# bpod_stepper_1_4_3.net
KiCad netlist of a schematic drawn in EAGLE
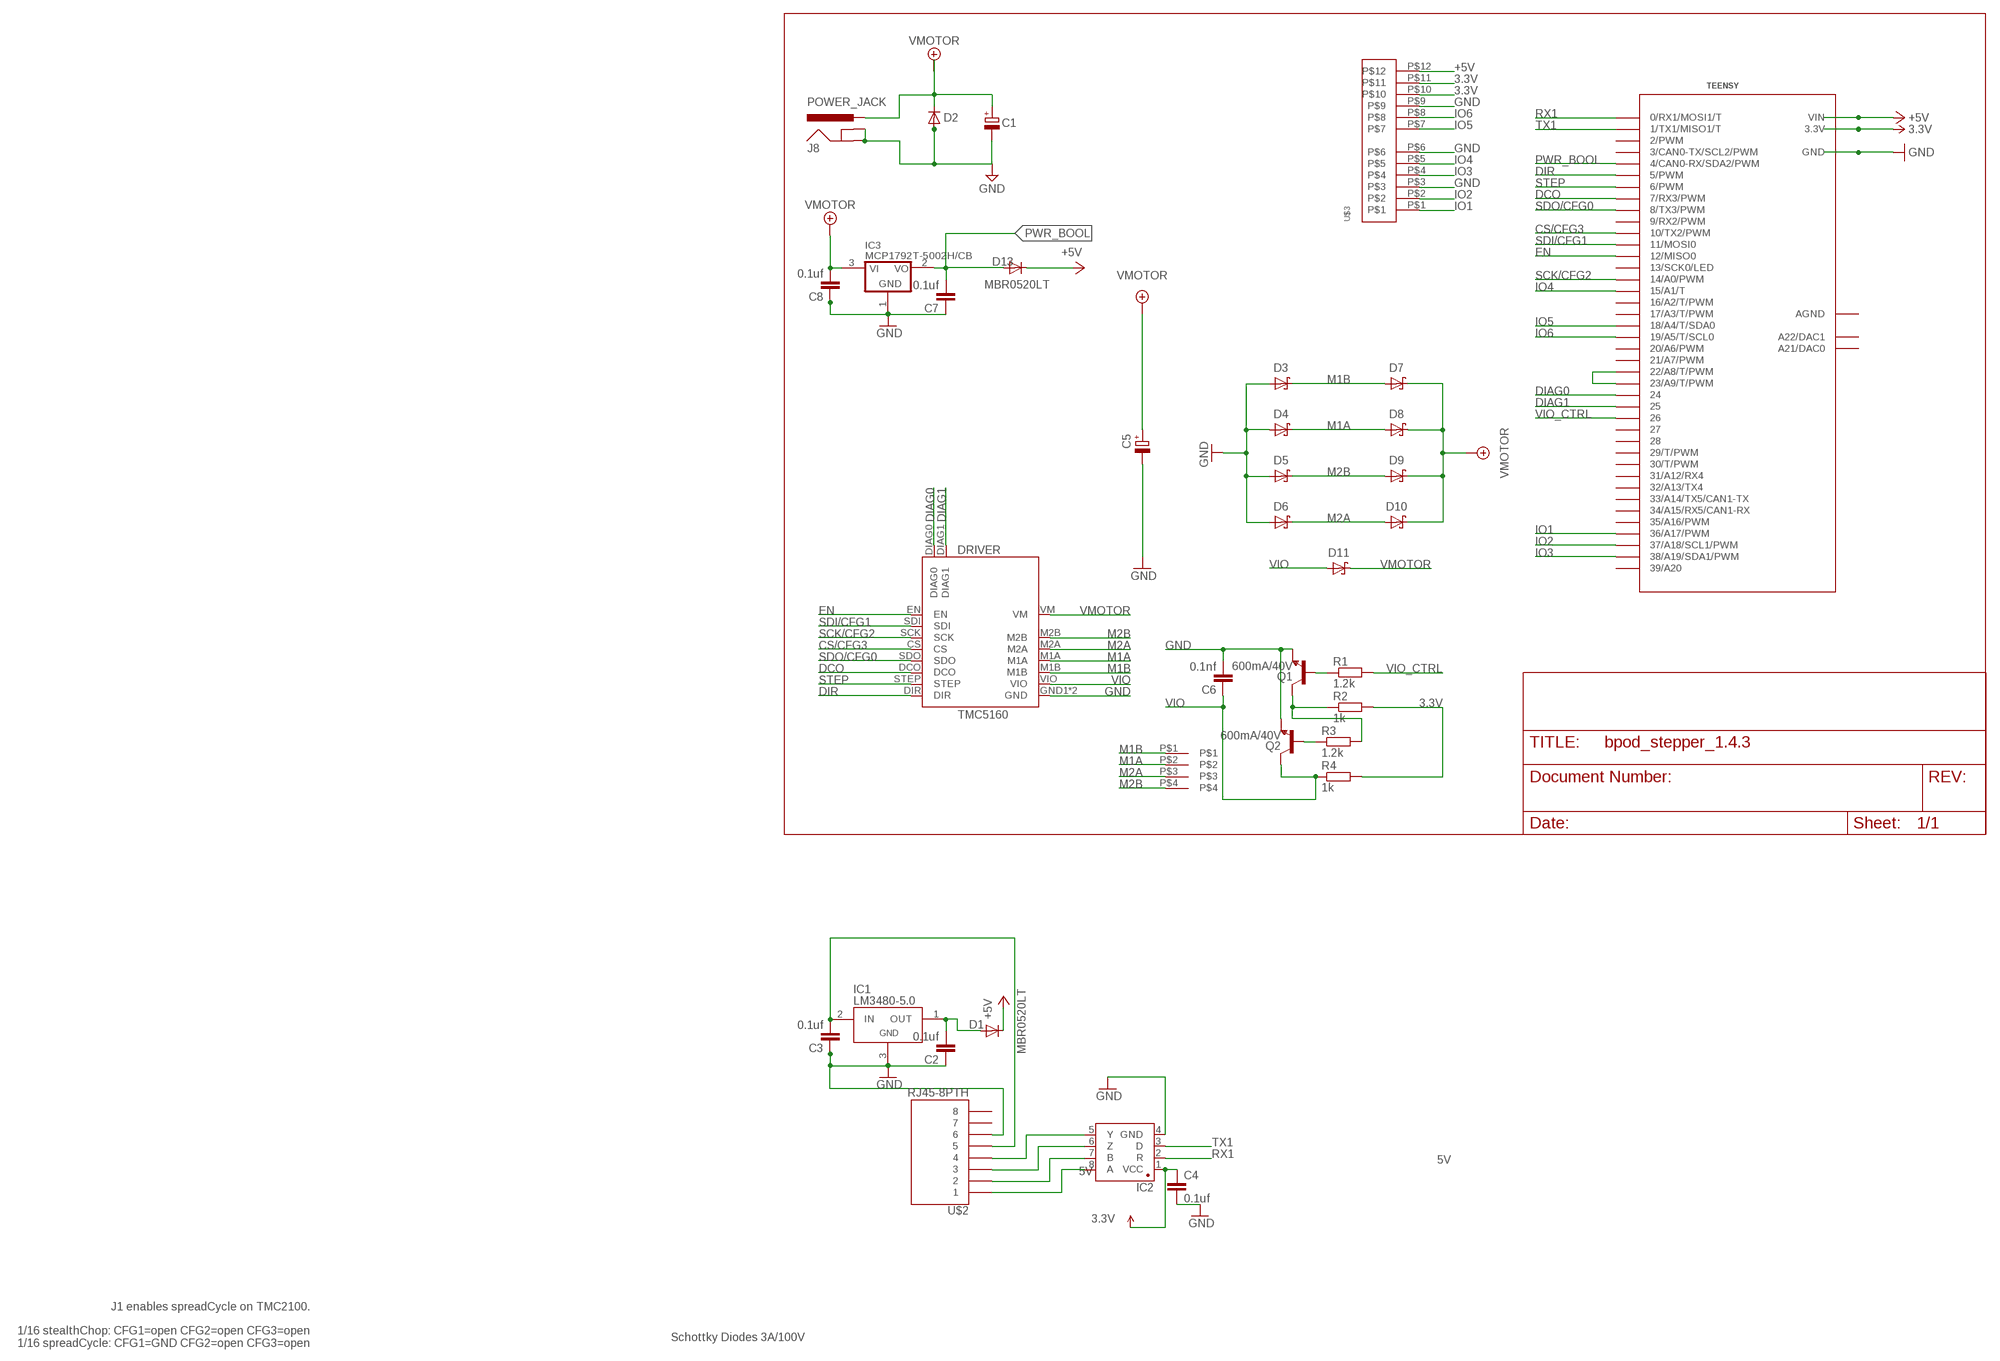
[diagram p0: schematic, sheet 1]

(export (version "E")
  (design (tool "Eeschema 10.0.6"))
  (components
    (comp (ref "C1")
      (value "CPOL-EUG")
      (footprint "eagle-import:PANASONIC_G")
      (libsource (lib "eagle-import") (part "CPOL-EUG"))
    )
    (comp (ref "C2")
      (value "0.1uf")
      (footprint "eagle-import:1206@1")
      (libsource (lib "eagle-import") (part "CAP1206"))
    )
    (comp (ref "C3")
      (value "0.1uf")
      (footprint "eagle-import:1206@1")
      (libsource (lib "eagle-import") (part "CAP1206"))
    )
    (comp (ref "C4")
      (value "0.1uf")
      (footprint "eagle-import:1206@1")
      (libsource (lib "eagle-import") (part "CAP1206"))
    )
    (comp (ref "C5")
      (value "CPOL-EUG")
      (footprint "eagle-import:PANASONIC_G")
      (libsource (lib "eagle-import") (part "CPOL-EUG"))
    )
    (comp (ref "C6")
      (value "0.1nf")
      (footprint "eagle-import:1206@1")
      (libsource (lib "eagle-import") (part "CAP1206"))
    )
    (comp (ref "C7")
      (value "0.1uf")
      (footprint "eagle-import:1206@1")
      (libsource (lib "eagle-import") (part "CAP1206"))
    )
    (comp (ref "C8")
      (value "0.1uf")
      (footprint "eagle-import:1206@1")
      (libsource (lib "eagle-import") (part "CAP1206"))
    )
    (comp (ref "D1")
      (value "MBR0520LT")
      (footprint "eagle-import:SOD123")
      (libsource (lib "eagle-import") (part "MBR0520LT"))
    )
    (comp (ref "D2")
      (value "DIODE-DO214AA")
      (footprint "eagle-import:DO214AA")
      (libsource (lib "eagle-import") (part "DIODE-DO214AA"))
    )
    (comp (ref "D3")
      (value "S310FA")
      (footprint "eagle-import:SOD123")
      (libsource (lib "eagle-import") (part "D_SCHOTTKY-SOD123"))
    )
    (comp (ref "D4")
      (value "S310FA")
      (footprint "eagle-import:SOD123")
      (libsource (lib "eagle-import") (part "D_SCHOTTKY-SOD123"))
    )
    (comp (ref "D5")
      (value "S310FA")
      (footprint "eagle-import:SOD123")
      (libsource (lib "eagle-import") (part "D_SCHOTTKY-SOD123"))
    )
    (comp (ref "D6")
      (value "S310FA")
      (footprint "eagle-import:SOD123")
      (libsource (lib "eagle-import") (part "D_SCHOTTKY-SOD123"))
    )
    (comp (ref "D7")
      (value "S310FA")
      (footprint "eagle-import:SOD123")
      (libsource (lib "eagle-import") (part "D_SCHOTTKY-SOD123"))
    )
    (comp (ref "D8")
      (value "S310FA")
      (footprint "eagle-import:SOD123")
      (libsource (lib "eagle-import") (part "D_SCHOTTKY-SOD123"))
    )
    (comp (ref "D9")
      (value "S310FA")
      (footprint "eagle-import:SOD123")
      (libsource (lib "eagle-import") (part "D_SCHOTTKY-SOD123"))
    )
    (comp (ref "D10")
      (value "S310FA")
      (footprint "eagle-import:SOD123")
      (libsource (lib "eagle-import") (part "D_SCHOTTKY-SOD123"))
    )
    (comp (ref "D11")
      (value "S310FA")
      (footprint "eagle-import:SOD123")
      (libsource (lib "eagle-import") (part "D_SCHOTTKY-SOD123"))
    )
    (comp (ref "D13")
      (value "MBR0520LT")
      (footprint "eagle-import:SOD123")
      (libsource (lib "eagle-import") (part "MBR0520LT"))
    )
    (comp (ref "DRIVER")
      (value "TMC5160")
      (footprint "eagle-import:TMC5160")
      (libsource (lib "eagle-import") (part "TMC5160"))
    )
    (comp (ref "IC1")
      (value "LM3480-5.0")
      (footprint "eagle-import:SOT-23-3")
      (libsource (lib "eagle-import") (part "LM3480-5.0"))
    )
    (comp (ref "IC2")
      (value "SN65HVD31DR")
      (footprint "eagle-import:SO08")
      (libsource (lib "eagle-import") (part "SN65HVD31DR"))
    )
    (comp (ref "IC3")
      (value "MCP1792T-5002H/CB")
      (footprint "eagle-import:SOT23A_MICROCHIP_CB")
      (libsource (lib "eagle-import") (part "MCP170302E/CB-12"))
    )
    (comp (ref "J8")
      (value "POWER_JACK")
      (footprint "eagle-import:POWER_JACK_PTH")
      (libsource (lib "eagle-import") (part "POWER_JACK"))
    )
    (comp (ref "Q1")
      (value "600mA/40V")
      (footprint "eagle-import:SOT23-3")
      (libsource (lib "eagle-import") (part "TRANS_NPN-MMBT2222AL"))
    )
    (comp (ref "Q2")
      (value "600mA/40V")
      (footprint "eagle-import:SOT23-3")
      (libsource (lib "eagle-import") (part "TRANS_NPN-MMBT2222AL"))
    )
    (comp (ref "R1")
      (value "1.2k")
      (footprint "eagle-import:R1206")
      (libsource (lib "eagle-import") (part "R-EU_R1206"))
    )
    (comp (ref "R2")
      (value "1k")
      (footprint "eagle-import:R1206")
      (libsource (lib "eagle-import") (part "R-EU_R1206"))
    )
    (comp (ref "R3")
      (value "1.2k")
      (footprint "eagle-import:R1206")
      (libsource (lib "eagle-import") (part "R-EU_R1206"))
    )
    (comp (ref "R4")
      (value "1k")
      (footprint "eagle-import:R1206")
      (libsource (lib "eagle-import") (part "R-EU_R1206"))
    )
    (comp (ref "TEENSY")
      (value "TEENSY_3.6_DIL")
      (footprint "eagle-import:TEENSY_3.6_DIL")
      (libsource (lib "eagle-import") (part "TEENSY_3.6_DIL"))
    )
    (comp (ref "U$2")
      (value "RJ45-8PTH")
      (footprint "eagle-import:RJ45-8")
      (libsource (lib "eagle-import") (part "RJ45-8PTH"))
    )
    (comp (ref "U$3")
      (value "12POS_MOLEX_SOCKET")
      (footprint "eagle-import:12POS_MOLEX_SOCKET")
      (libsource (lib "eagle-import") (part "12POS_MOLEX_SOCKET"))
    )
    (comp (ref "U$4")
      (value "MOLEX395221004")
      (footprint "eagle-import:MOLEX395221004")
      (libsource (lib "eagle-import") (part "MOLEX395221004"))
    )
  )
  (nets
    (net (code "1") (name "+5V") (class "Default")
      (node (ref "D1") (pin "C") (pinfunction "C_C") (pintype "passive"))
      (node (ref "D13") (pin "C") (pinfunction "C_C") (pintype "passive"))
      (node (ref "TEENSY") (pin "VIN") (pinfunction "VIN_VIN") (pintype "power_in"))
      (node (ref "U$3") (pin "P$12") (pinfunction "P$12_P$12") (pintype "bidirectional"))
    )
    (net (code "2") (name "/AGND") (class "Default")
      (node (ref "TEENSY") (pin "AGND") (pinfunction "AGND_AGND") (pintype "power_in"))
    )
    (net (code "3") (name "/CS{slash}CFG3") (class "Default")
      (node (ref "DRIVER") (pin "CS") (pinfunction "CS_CS") (pintype "passive"))
      (node (ref "TEENSY") (pin "10") (pinfunction "10/TX2/PWM_10") (pintype "bidirectional"))
    )
    (net (code "4") (name "/DCO") (class "Default")
      (node (ref "DRIVER") (pin "DCO") (pinfunction "DCO_DCO") (pintype "passive"))
      (node (ref "TEENSY") (pin "7") (pinfunction "7/RX3/PWM_7") (pintype "bidirectional"))
    )
    (net (code "5") (name "/DIAG0") (class "Default")
      (node (ref "DRIVER") (pin "DIAG0") (pinfunction "DIAG0_DIAG0") (pintype "passive"))
      (node (ref "TEENSY") (pin "24") (pinfunction "24_24") (pintype "bidirectional"))
    )
    (net (code "6") (name "/DIAG1") (class "Default")
      (node (ref "DRIVER") (pin "DIAG1") (pinfunction "DIAG1_DIAG1") (pintype "passive"))
      (node (ref "TEENSY") (pin "25") (pinfunction "25_25") (pintype "bidirectional"))
    )
    (net (code "7") (name "/DIR") (class "Default")
      (node (ref "DRIVER") (pin "DIR") (pinfunction "DIR_DIR") (pintype "input"))
      (node (ref "TEENSY") (pin "5") (pinfunction "5/PWM_5") (pintype "bidirectional"))
    )
    (net (code "8") (name "/EN") (class "Default")
      (node (ref "DRIVER") (pin "EN") (pinfunction "EN_EN") (pintype "passive"))
      (node (ref "TEENSY") (pin "12") (pinfunction "12/MISO0_12") (pintype "bidirectional"))
    )
    (net (code "9") (name "/IO1") (class "Default")
      (node (ref "TEENSY") (pin "36/A17") (pinfunction "36/A17/PWM_36/A17") (pintype "bidirectional"))
      (node (ref "U$3") (pin "P$1") (pinfunction "P$1_P$1") (pintype "bidirectional"))
    )
    (net (code "10") (name "/IO2") (class "Default")
      (node (ref "TEENSY") (pin "37/A18") (pinfunction "37/A18/SCL1/PWM_37/A18") (pintype "bidirectional"))
      (node (ref "U$3") (pin "P$2") (pinfunction "P$2_P$2") (pintype "bidirectional"))
    )
    (net (code "11") (name "/IO3") (class "Default")
      (node (ref "TEENSY") (pin "38/A19") (pinfunction "38/A19/SDA1/PWM_38/A19") (pintype "bidirectional"))
      (node (ref "U$3") (pin "P$4") (pinfunction "P$4_P$4") (pintype "bidirectional"))
    )
    (net (code "12") (name "/IO4") (class "Default")
      (node (ref "TEENSY") (pin "15/A1") (pinfunction "15/A1/T_15/A1") (pintype "bidirectional"))
      (node (ref "U$3") (pin "P$5") (pinfunction "P$5_P$5") (pintype "bidirectional"))
    )
    (net (code "13") (name "/IO5") (class "Default")
      (node (ref "TEENSY") (pin "18/A4") (pinfunction "18/A4/T/SDA0_18/A4") (pintype "bidirectional"))
      (node (ref "U$3") (pin "P$7") (pinfunction "P$7_P$7") (pintype "bidirectional"))
    )
    (net (code "14") (name "/IO6") (class "Default")
      (node (ref "TEENSY") (pin "19/A5") (pinfunction "19/A5/T/SCL0_19/A5") (pintype "bidirectional"))
      (node (ref "U$3") (pin "P$8") (pinfunction "P$8_P$8") (pintype "bidirectional"))
    )
    (net (code "15") (name "/M1A") (class "Default")
      (node (ref "D4") (pin "C") (pinfunction "C_C") (pintype "passive"))
      (node (ref "D8") (pin "A") (pinfunction "A_A") (pintype "passive"))
      (node (ref "DRIVER") (pin "M1A") (pinfunction "M1A_M1A") (pintype "output"))
      (node (ref "U$4") (pin "P$2") (pinfunction "P$2_P$2") (pintype "bidirectional"))
    )
    (net (code "16") (name "/M1B") (class "Default")
      (node (ref "D3") (pin "C") (pinfunction "C_C") (pintype "passive"))
      (node (ref "D7") (pin "A") (pinfunction "A_A") (pintype "passive"))
      (node (ref "DRIVER") (pin "M1B") (pinfunction "M1B_M1B") (pintype "output"))
      (node (ref "U$4") (pin "P$1") (pinfunction "P$1_P$1") (pintype "bidirectional"))
    )
    (net (code "17") (name "/M2A") (class "Default")
      (node (ref "D10") (pin "A") (pinfunction "A_A") (pintype "passive"))
      (node (ref "D6") (pin "C") (pinfunction "C_C") (pintype "passive"))
      (node (ref "DRIVER") (pin "M2A") (pinfunction "M2A_M2A") (pintype "output"))
      (node (ref "U$4") (pin "P$3") (pinfunction "P$3_P$3") (pintype "bidirectional"))
    )
    (net (code "18") (name "/M2B") (class "Default")
      (node (ref "D5") (pin "C") (pinfunction "C_C") (pintype "passive"))
      (node (ref "D9") (pin "A") (pinfunction "A_A") (pintype "passive"))
      (node (ref "DRIVER") (pin "M2B") (pinfunction "M2B_M2B") (pintype "output"))
      (node (ref "U$4") (pin "P$4") (pinfunction "P$4_P$4") (pintype "bidirectional"))
    )
    (net (code "19") (name "/RX1") (class "Default")
      (node (ref "IC2") (pin "2") (pinfunction "R_2") (pintype "bidirectional"))
      (node (ref "TEENSY") (pin "0") (pinfunction "0/RX1/MOSI1/T_0") (pintype "bidirectional"))
    )
    (net (code "20") (name "/SCK{slash}CFG2") (class "Default")
      (node (ref "DRIVER") (pin "SCK") (pinfunction "SCK_SCK") (pintype "passive"))
      (node (ref "TEENSY") (pin "14/A0") (pinfunction "14/A0/PWM_14/A0") (pintype "bidirectional"))
    )
    (net (code "21") (name "/SDI{slash}CFG1") (class "Default")
      (node (ref "DRIVER") (pin "SDI") (pinfunction "SDI_SDI") (pintype "passive"))
      (node (ref "TEENSY") (pin "11") (pinfunction "11/MOSI0_11") (pintype "bidirectional"))
    )
    (net (code "22") (name "/SDO{slash}CFG0") (class "Default")
      (node (ref "DRIVER") (pin "SDO") (pinfunction "SDO_SDO") (pintype "passive"))
      (node (ref "TEENSY") (pin "8") (pinfunction "8/TX3/PWM_8") (pintype "bidirectional"))
    )
    (net (code "23") (name "/STEP") (class "Default")
      (node (ref "DRIVER") (pin "STEP") (pinfunction "STEP_STEP") (pintype "input"))
      (node (ref "TEENSY") (pin "6") (pinfunction "6/PWM_6") (pintype "bidirectional"))
    )
    (net (code "24") (name "/TX1") (class "Default")
      (node (ref "IC2") (pin "3") (pinfunction "D_3") (pintype "bidirectional"))
      (node (ref "TEENSY") (pin "1") (pinfunction "1/TX1/MISO1/T_1") (pintype "bidirectional"))
    )
    (net (code "25") (name "/VIO") (class "Default")
      (node (ref "C6") (pin "1") (pinfunction "1_1") (pintype "passive"))
      (node (ref "D11") (pin "A") (pinfunction "A_A") (pintype "passive"))
      (node (ref "DRIVER") (pin "VIO") (pinfunction "VIO_VIO") (pintype "power_in"))
      (node (ref "Q2") (pin "3") (pinfunction "C_3") (pintype "passive"))
      (node (ref "R4") (pin "1") (pinfunction "1_1") (pintype "passive"))
    )
    (net (code "26") (name "/VIO_CTRL") (class "Default")
      (node (ref "R1") (pin "2") (pinfunction "2_2") (pintype "passive"))
      (node (ref "TEENSY") (pin "26") (pinfunction "26_26") (pintype "bidirectional"))
    )
    (net (code "27") (name "3.3V") (class "Default")
      (node (ref "C4") (pin "1") (pinfunction "1_1") (pintype "passive"))
      (node (ref "IC2") (pin "1") (pinfunction "VCC_1") (pintype "bidirectional"))
      (node (ref "R2") (pin "2") (pinfunction "2_2") (pintype "passive"))
      (node (ref "R4") (pin "2") (pinfunction "2_2") (pintype "passive"))
      (node (ref "TEENSY") (pin "3.3V") (pinfunction "3.3V_3.3V") (pintype "power_in"))
      (node (ref "TEENSY") (pin "3.3V3") (pinfunction "3.3V_3.3V3") (pintype "power_in"))
      (node (ref "U$3") (pin "P$10") (pinfunction "P$10_P$10") (pintype "bidirectional"))
      (node (ref "U$3") (pin "P$11") (pinfunction "P$11_P$11") (pintype "bidirectional"))
    )
    (net (code "28") (name "GND") (class "Default")
      (node (ref "C1") (pin "-") (pinfunction "-_-") (pintype "passive"))
      (node (ref "C2") (pin "1") (pinfunction "1_1") (pintype "passive"))
      (node (ref "C3") (pin "1") (pinfunction "1_1") (pintype "passive"))
      (node (ref "C4") (pin "2") (pinfunction "2_2") (pintype "passive"))
      (node (ref "C5") (pin "-") (pinfunction "-_-") (pintype "passive"))
      (node (ref "C6") (pin "2") (pinfunction "2_2") (pintype "passive"))
      (node (ref "C7") (pin "1") (pinfunction "1_1") (pintype "passive"))
      (node (ref "C8") (pin "1") (pinfunction "1_1") (pintype "passive"))
      (node (ref "D2") (pin "A") (pinfunction "A_A") (pintype "passive"))
      (node (ref "D3") (pin "A") (pinfunction "A_A") (pintype "passive"))
      (node (ref "D4") (pin "A") (pinfunction "A_A") (pintype "passive"))
      (node (ref "D5") (pin "A") (pinfunction "A_A") (pintype "passive"))
      (node (ref "D6") (pin "A") (pinfunction "A_A") (pintype "passive"))
      (node (ref "DRIVER") (pin "GND1") (pinfunction "GND_GND1") (pintype "power_in"))
      (node (ref "DRIVER") (pin "GND2") (pinfunction "GND_GND2") (pintype "power_in"))
      (node (ref "IC1") (pin "3") (pinfunction "GND_3") (pintype "power_in"))
      (node (ref "IC2") (pin "4") (pinfunction "GND_4") (pintype "bidirectional"))
      (node (ref "IC3") (pin "1") (pinfunction "GND_1") (pintype "power_in"))
      (node (ref "J8") (pin "GND") (pinfunction "GND_GND") (pintype "bidirectional"))
      (node (ref "J8") (pin "GNDBREAK") (pinfunction "GNDBREAK_GNDBREAK") (pintype "bidirectional"))
      (node (ref "Q1") (pin "2") (pinfunction "E_2") (pintype "passive"))
      (node (ref "Q2") (pin "2") (pinfunction "E_2") (pintype "passive"))
      (node (ref "TEENSY") (pin "GND") (pinfunction "GND_GND") (pintype "power_in"))
      (node (ref "TEENSY") (pin "GND1") (pinfunction "GND_GND1") (pintype "power_in"))
      (node (ref "U$2") (pin "6") (pinfunction "6_6") (pintype "bidirectional"))
      (node (ref "U$3") (pin "P$3") (pinfunction "P$3_P$3") (pintype "bidirectional"))
      (node (ref "U$3") (pin "P$6") (pinfunction "P$6_P$6") (pintype "bidirectional"))
      (node (ref "U$3") (pin "P$9") (pinfunction "P$9_P$9") (pintype "bidirectional"))
    )
    (net (code "29") (name "Net-(IC1-IN)") (class "Default")
      (node (ref "C3") (pin "2") (pinfunction "2_2") (pintype "passive"))
      (node (ref "IC1") (pin "2") (pinfunction "IN_2") (pintype "power_in"))
      (node (ref "U$2") (pin "5") (pinfunction "5_5") (pintype "bidirectional"))
    )
    (net (code "30") (name "Net-(IC1-OUT)") (class "Default")
      (node (ref "C2") (pin "2") (pinfunction "2_2") (pintype "passive"))
      (node (ref "D1") (pin "A") (pinfunction "A_A") (pintype "passive"))
      (node (ref "IC1") (pin "1") (pinfunction "OUT_1") (pintype "power_in"))
    )
    (net (code "31") (name "Net-(IC2-A)") (class "Default")
      (node (ref "IC2") (pin "8") (pinfunction "A_8") (pintype "bidirectional"))
      (node (ref "U$2") (pin "1") (pinfunction "1_1") (pintype "bidirectional"))
    )
    (net (code "32") (name "Net-(IC2-B)") (class "Default")
      (node (ref "IC2") (pin "7") (pinfunction "B_7") (pintype "bidirectional"))
      (node (ref "U$2") (pin "2") (pinfunction "2_2") (pintype "bidirectional"))
    )
    (net (code "33") (name "Net-(IC2-Y)") (class "Default")
      (node (ref "IC2") (pin "5") (pinfunction "Y_5") (pintype "bidirectional"))
      (node (ref "U$2") (pin "4") (pinfunction "4_4") (pintype "bidirectional"))
    )
    (net (code "34") (name "Net-(IC2-Z)") (class "Default")
      (node (ref "IC2") (pin "6") (pinfunction "Z_6") (pintype "bidirectional"))
      (node (ref "U$2") (pin "3") (pinfunction "3_3") (pintype "bidirectional"))
    )
    (net (code "35") (name "Net-(Q1-B)") (class "Default")
      (node (ref "Q1") (pin "1") (pinfunction "B_1") (pintype "passive"))
      (node (ref "R1") (pin "1") (pinfunction "1_1") (pintype "passive"))
    )
    (net (code "36") (name "Net-(Q1-C)") (class "Default")
      (node (ref "Q1") (pin "3") (pinfunction "C_3") (pintype "passive"))
      (node (ref "R2") (pin "1") (pinfunction "1_1") (pintype "passive"))
      (node (ref "R3") (pin "2") (pinfunction "2_2") (pintype "passive"))
    )
    (net (code "37") (name "Net-(Q2-B)") (class "Default")
      (node (ref "Q2") (pin "1") (pinfunction "B_1") (pintype "passive"))
      (node (ref "R3") (pin "1") (pinfunction "1_1") (pintype "passive"))
    )
    (net (code "38") (name "Net-(TEENSY-22{slash}A8{slash}T{slash}PWM)") (class "Default")
      (node (ref "TEENSY") (pin "22/A8") (pinfunction "22/A8/T/PWM_22/A8") (pintype "bidirectional"))
      (node (ref "TEENSY") (pin "23/A9") (pinfunction "23/A9/T/PWM_23/A9") (pintype "bidirectional"))
    )
    (net (code "39") (name "PWR_BOOL") (class "Default")
      (node (ref "C7") (pin "2") (pinfunction "2_2") (pintype "passive"))
      (node (ref "D13") (pin "A") (pinfunction "A_A") (pintype "passive"))
      (node (ref "IC3") (pin "2") (pinfunction "VO_2") (pintype "passive"))
      (node (ref "TEENSY") (pin "4") (pinfunction "4/CAN0-RX/SDA2/PWM_4") (pintype "bidirectional"))
    )
    (net (code "40") (name "VMOTOR") (class "Default")
      (node (ref "C1") (pin "+") (pinfunction "+_+") (pintype "passive"))
      (node (ref "C5") (pin "+") (pinfunction "+_+") (pintype "passive"))
      (node (ref "C8") (pin "2") (pinfunction "2_2") (pintype "passive"))
      (node (ref "D10") (pin "C") (pinfunction "C_C") (pintype "passive"))
      (node (ref "D11") (pin "C") (pinfunction "C_C") (pintype "passive"))
      (node (ref "D2") (pin "C") (pinfunction "C_C") (pintype "passive"))
      (node (ref "D7") (pin "C") (pinfunction "C_C") (pintype "passive"))
      (node (ref "D8") (pin "C") (pinfunction "C_C") (pintype "passive"))
      (node (ref "D9") (pin "C") (pinfunction "C_C") (pintype "passive"))
      (node (ref "DRIVER") (pin "VM") (pinfunction "VM_VM") (pintype "power_in"))
      (node (ref "IC3") (pin "3") (pinfunction "VI_3") (pintype "power_in"))
      (node (ref "J8") (pin "PWR") (pinfunction "PWR_PWR") (pintype "bidirectional"))
    )
    (net (code "41") (name "unconnected-(TEENSY-2{slash}PWM-Pad2)") (class "Default")
      (node (ref "TEENSY") (pin "2") (pinfunction "2/PWM_2") (pintype "bidirectional"))
    )
    (net (code "42") (name "unconnected-(TEENSY-3{slash}CAN0-TX{slash}SCL2{slash}PWM-Pad3)") (class "Default")
      (node (ref "TEENSY") (pin "3") (pinfunction "3/CAN0-TX/SCL2/PWM_3") (pintype "bidirectional"))
    )
    (net (code "43") (name "unconnected-(TEENSY-9{slash}RX2{slash}PWM-Pad9)") (class "Default")
      (node (ref "TEENSY") (pin "9") (pinfunction "9/RX2/PWM_9") (pintype "bidirectional"))
    )
    (net (code "44") (name "unconnected-(TEENSY-13{slash}SCK0{slash}LED-Pad13)") (class "Default")
      (node (ref "TEENSY") (pin "13") (pinfunction "13/SCK0/LED_13") (pintype "bidirectional"))
    )
    (net (code "45") (name "unconnected-(TEENSY-16{slash}A2{slash}T{slash}PWM-Pad16{slash}A2)") (class "Default")
      (node (ref "TEENSY") (pin "16/A2") (pinfunction "16/A2/T/PWM_16/A2") (pintype "bidirectional"))
    )
    (net (code "46") (name "unconnected-(TEENSY-17{slash}A3{slash}T{slash}PWM-Pad17{slash}A3)") (class "Default")
      (node (ref "TEENSY") (pin "17/A3") (pinfunction "17/A3/T/PWM_17/A3") (pintype "bidirectional"))
    )
    (net (code "47") (name "unconnected-(TEENSY-20{slash}A6{slash}PWM-Pad20{slash}A6)") (class "Default")
      (node (ref "TEENSY") (pin "20/A6") (pinfunction "20/A6/PWM_20/A6") (pintype "bidirectional"))
    )
    (net (code "48") (name "unconnected-(TEENSY-21{slash}A7{slash}PWM-Pad21{slash}A7)") (class "Default")
      (node (ref "TEENSY") (pin "21/A7") (pinfunction "21/A7/PWM_21/A7") (pintype "bidirectional"))
    )
    (net (code "49") (name "unconnected-(TEENSY-29{slash}T{slash}PWM-Pad29)") (class "Default")
      (node (ref "TEENSY") (pin "29") (pinfunction "29/T/PWM_29") (pintype "bidirectional"))
    )
    (net (code "50") (name "unconnected-(TEENSY-30{slash}T{slash}PWM-Pad30)") (class "Default")
      (node (ref "TEENSY") (pin "30") (pinfunction "30/T/PWM_30") (pintype "bidirectional"))
    )
    (net (code "51") (name "unconnected-(TEENSY-31{slash}A12{slash}RX4-Pad31{slash}A12)") (class "Default")
      (node (ref "TEENSY") (pin "31/A12") (pinfunction "31/A12/RX4_31/A12") (pintype "bidirectional"))
    )
    (net (code "52") (name "unconnected-(TEENSY-32{slash}A13{slash}TX4-Pad32{slash}A13)") (class "Default")
      (node (ref "TEENSY") (pin "32/A13") (pinfunction "32/A13/TX4_32/A13") (pintype "bidirectional"))
    )
    (net (code "53") (name "unconnected-(TEENSY-33{slash}A14{slash}TX5{slash}CAN1-TX-Pad33{slash}A14)") (class "Default")
      (node (ref "TEENSY") (pin "33/A14") (pinfunction "33/A14/TX5/CAN1-TX_33/A14") (pintype "bidirectional"))
    )
    (net (code "54") (name "unconnected-(TEENSY-34{slash}A15{slash}RX5{slash}CAN1-RX-Pad34{slash}A15)") (class "Default")
      (node (ref "TEENSY") (pin "34/A15") (pinfunction "34/A15/RX5/CAN1-RX_34/A15") (pintype "bidirectional"))
    )
    (net (code "55") (name "unconnected-(TEENSY-35{slash}A16{slash}PWM-Pad35{slash}A16)") (class "Default")
      (node (ref "TEENSY") (pin "35/A16") (pinfunction "35/A16/PWM_35/A16") (pintype "bidirectional"))
    )
    (net (code "56") (name "unconnected-(TEENSY-A21{slash}DAC0-PadA21)") (class "Default")
      (node (ref "TEENSY") (pin "A21") (pinfunction "A21/DAC0_A21") (pintype "bidirectional"))
    )
    (net (code "57") (name "unconnected-(TEENSY-A22{slash}DAC1-PadA22)") (class "Default")
      (node (ref "TEENSY") (pin "A22") (pinfunction "A22/DAC1_A22") (pintype "bidirectional"))
    )
    (net (code "58") (name "unconnected-(TEENSY-Pad27)") (class "Default")
      (node (ref "TEENSY") (pin "27") (pinfunction "27_27") (pintype "bidirectional"))
    )
    (net (code "59") (name "unconnected-(TEENSY-Pad28)") (class "Default")
      (node (ref "TEENSY") (pin "28") (pinfunction "28_28") (pintype "bidirectional"))
    )
    (net (code "60") (name "unconnected-(TEENSY-Pad39{slash}A20)") (class "Default")
      (node (ref "TEENSY") (pin "39/A20") (pinfunction "39/A20_39/A20") (pintype "bidirectional"))
    )
    (net (code "61") (name "unconnected-(U$2-Pad7)") (class "Default")
      (node (ref "U$2") (pin "7") (pinfunction "7_7") (pintype "bidirectional"))
    )
    (net (code "62") (name "unconnected-(U$2-Pad8)") (class "Default")
      (node (ref "U$2") (pin "8") (pinfunction "8_8") (pintype "bidirectional"))
    )
  )
)
